# WirelessPowerRxExtensionBoard.net
KiCad netlist of a schematic drawn in EAGLE
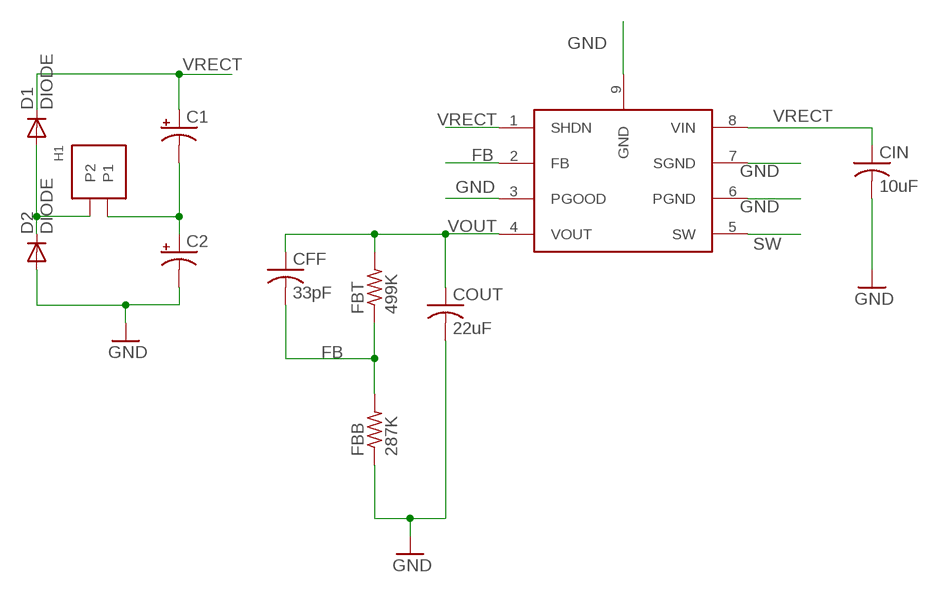
[diagram p0: schematic, sheet 1]

(export (version "E")
  (design (tool "Eeschema 10.0.6"))
  (components
    (comp (ref "C1")
      (value "CPOL-USE5-13")
      (footprint "eagle-import:E5-13")
      (libsource (lib "eagle-import") (part "CPOL-USE5-13"))
    )
    (comp (ref "C2")
      (value "CPOL-USE5-13")
      (footprint "eagle-import:E5-13")
      (libsource (lib "eagle-import") (part "CPOL-USE5-13"))
    )
    (comp (ref "CFF")
      (value "33pF")
      (footprint "eagle-import:C0201")
      (libsource (lib "eagle-import") (part "C-USC0201"))
    )
    (comp (ref "CIN")
      (value "10uF")
      (footprint "eagle-import:C0805")
      (libsource (lib "eagle-import") (part "resistor_C-USC0805"))
    )
    (comp (ref "COUT")
      (value "22uF")
      (footprint "eagle-import:C0805")
      (libsource (lib "eagle-import") (part "resistor_C-USC0805"))
    )
    (comp (ref "D1")
      (value "DIODE")
      (footprint "eagle-import:DO-214AB")
      (libsource (lib "eagle-import") (part "DIODE"))
    )
    (comp (ref "D2")
      (value "DIODE")
      (footprint "eagle-import:DO-214AB")
      (libsource (lib "eagle-import") (part "DIODE"))
    )
    (comp (ref "FBB")
      (value "287K")
      (footprint "eagle-import:M0805")
      (libsource (lib "eagle-import") (part "R-US_M0805"))
    )
    (comp (ref "FBT")
      (value "499K")
      (footprint "eagle-import:M0805")
      (libsource (lib "eagle-import") (part "R-US_M0805"))
    )
    (comp (ref "H1")
      (value "DF3-2")
      (footprint "eagle-import:DF3-2")
      (libsource (lib "eagle-import") (part "DF3-2"))
    )
    (comp (ref "U$1")
      (value "STEPUPCONVERTER")
      (footprint "eagle-import:LTC3528_LTC3528B")
      (libsource (lib "eagle-import") (part "STEPUPCONVERTER"))
    )
  )
  (nets
    (net (code "1") (name "/FB") (class "Default")
      (node (ref "CFF") (pin "2") (pinfunction "2_2") (pintype "passive"))
      (node (ref "FBB") (pin "2") (pinfunction "2_2") (pintype "passive"))
      (node (ref "FBT") (pin "1") (pinfunction "1_1") (pintype "passive"))
      (node (ref "U$1") (pin "2") (pinfunction "FB_2") (pintype "bidirectional"))
    )
    (net (code "2") (name "/SW") (class "Default")
      (node (ref "U$1") (pin "5") (pinfunction "SW_5") (pintype "bidirectional"))
    )
    (net (code "3") (name "/VOUT") (class "Default")
      (node (ref "CFF") (pin "1") (pinfunction "1_1") (pintype "passive"))
      (node (ref "COUT") (pin "1") (pinfunction "1_1") (pintype "passive"))
      (node (ref "FBT") (pin "2") (pinfunction "2_2") (pintype "passive"))
      (node (ref "U$1") (pin "4") (pinfunction "VOUT_4") (pintype "output"))
    )
    (net (code "4") (name "/VRECT") (class "Default")
      (node (ref "C1") (pin "+") (pinfunction "+_+") (pintype "passive"))
      (node (ref "CIN") (pin "1") (pinfunction "1_1") (pintype "passive"))
      (node (ref "D1") (pin "P$1") (pinfunction "C_P$1") (pintype "passive"))
      (node (ref "U$1") (pin "1") (pinfunction "SHDN_1") (pintype "input"))
      (node (ref "U$1") (pin "8") (pinfunction "VIN_8") (pintype "input"))
    )
    (net (code "5") (name "GND") (class "Default")
      (node (ref "C2") (pin "-") (pinfunction "-_-") (pintype "passive"))
      (node (ref "CIN") (pin "2") (pinfunction "2_2") (pintype "passive"))
      (node (ref "COUT") (pin "2") (pinfunction "2_2") (pintype "passive"))
      (node (ref "D2") (pin "P$2") (pinfunction "A_P$2") (pintype "passive"))
      (node (ref "FBB") (pin "1") (pinfunction "1_1") (pintype "passive"))
      (node (ref "U$1") (pin "3") (pinfunction "PGOOD_3") (pintype "bidirectional"))
      (node (ref "U$1") (pin "6") (pinfunction "PGND_6") (pintype "bidirectional"))
      (node (ref "U$1") (pin "7") (pinfunction "SGND_7") (pintype "bidirectional"))
      (node (ref "U$1") (pin "9") (pinfunction "GND_9") (pintype "power_in"))
    )
    (net (code "6") (name "Net-(D1-A)") (class "Default")
      (node (ref "D1") (pin "P$2") (pinfunction "A_P$2") (pintype "passive"))
      (node (ref "D2") (pin "P$1") (pinfunction "C_P$1") (pintype "passive"))
      (node (ref "H1") (pin "P$2") (pinfunction "P2_P$2") (pintype "bidirectional"))
    )
    (net (code "7") (name "Net-(H1-P1)") (class "Default")
      (node (ref "C1") (pin "-") (pinfunction "-_-") (pintype "passive"))
      (node (ref "C2") (pin "+") (pinfunction "+_+") (pintype "passive"))
      (node (ref "H1") (pin "P$1") (pinfunction "P1_P$1") (pintype "bidirectional"))
    )
  )
)
